# ACL_Shield_V3.net
KiCad netlist of a schematic drawn in EAGLE
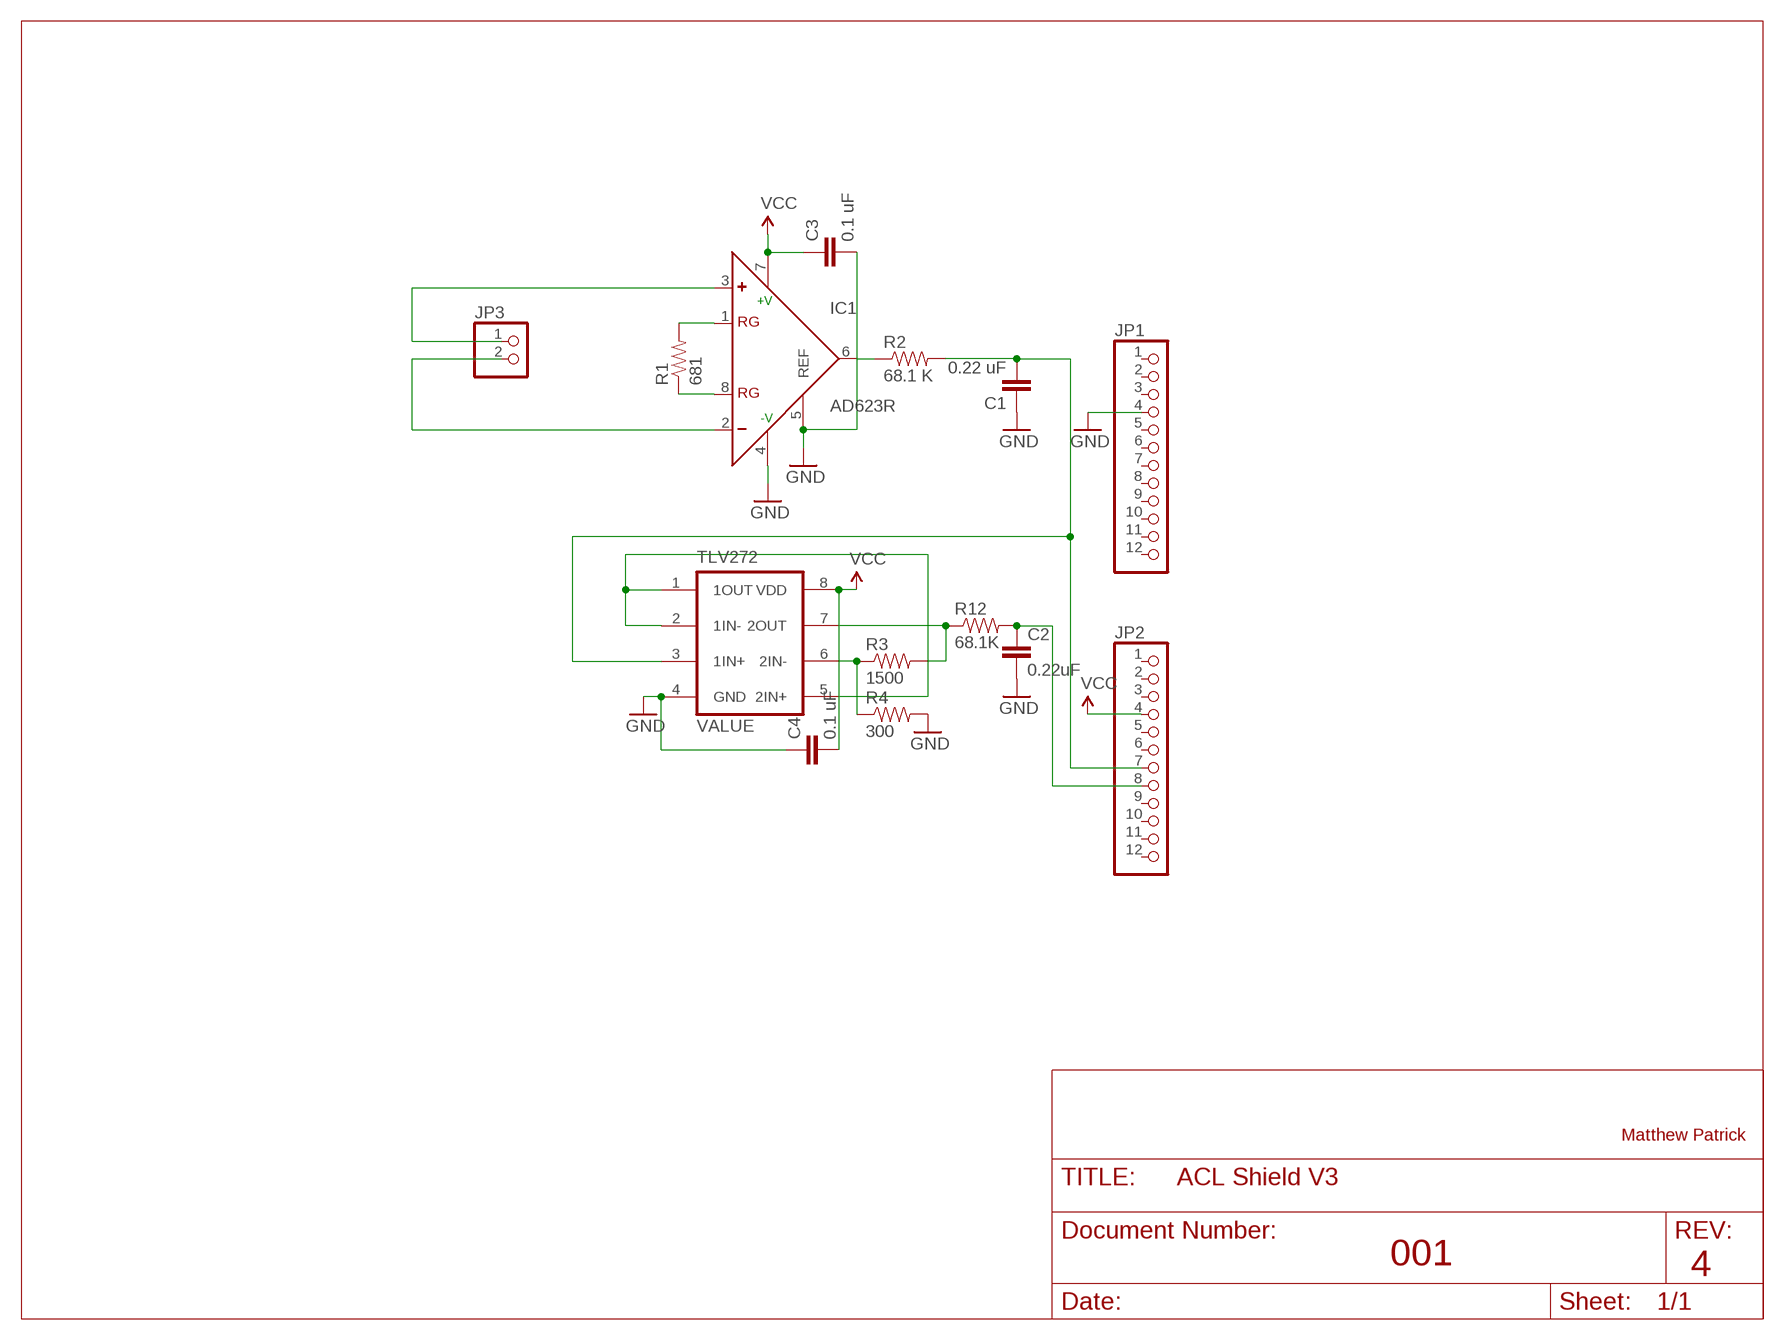
[diagram p0: schematic, sheet 1]

(export (version "E")
  (design (tool "Eeschema 10.0.6"))
  (components
    (comp (ref "C1")
      (value "0.22 uF")
      (footprint "eagle-import:0603-CAP")
      (libsource (lib "eagle-import") (part "CAP0603-CAP"))
    )
    (comp (ref "C2")
      (value "0.22uF")
      (footprint "eagle-import:0603-CAP")
      (libsource (lib "eagle-import") (part "CAP0603-CAP"))
    )
    (comp (ref "C3")
      (value "0.1 uF")
      (footprint "eagle-import:0603-CAP")
      (libsource (lib "eagle-import") (part "CAP0603-CAP"))
    )
    (comp (ref "C4")
      (value "0.1 uF")
      (footprint "eagle-import:0603-CAP")
      (libsource (lib "eagle-import") (part "CAP0603-CAP"))
    )
    (comp (ref "IC1")
      (value "AD623R")
      (footprint "eagle-import:SO8")
      (fields (field (name "MPN") "AD623ARZ."))
      (libsource (lib "eagle-import") (part "AD623R"))
    )
    (comp (ref "JP1")
      (value "PINHD-1X12")
      (footprint "eagle-import:1X12")
      (libsource (lib "eagle-import") (part "PINHD-1X12"))
    )
    (comp (ref "JP2")
      (value "PINHD-1X12")
      (footprint "eagle-import:1X12")
      (libsource (lib "eagle-import") (part "PINHD-1X12"))
    )
    (comp (ref "JP3")
      (value "PINHD-1X2")
      (footprint "eagle-import:1X02")
      (libsource (lib "eagle-import") (part "PINHD-1X2"))
    )
    (comp (ref "R1")
      (value "681")
      (footprint "eagle-import:0603-RES")
      (libsource (lib "eagle-import") (part "RESISTOR0603-RES"))
    )
    (comp (ref "R2")
      (value "68.1 K")
      (footprint "eagle-import:0603-RES")
      (libsource (lib "eagle-import") (part "RESISTOR0603-RES"))
    )
    (comp (ref "R3")
      (value "1500")
      (footprint "eagle-import:0603-RES")
      (libsource (lib "eagle-import") (part "RESISTOR0603-RES"))
    )
    (comp (ref "R4")
      (value "300")
      (footprint "eagle-import:0603-RES")
      (libsource (lib "eagle-import") (part "RESISTOR0603-RES"))
    )
    (comp (ref "R12")
      (value "68.1K")
      (footprint "eagle-import:0603-RES")
      (libsource (lib "eagle-import") (part "RESISTOR0603-RES"))
    )
    (comp (ref "U$2")
      (value "T2721")
      (footprint "eagle-import:SO-08")
      (libsource (lib "eagle-import") (part "T2721"))
    )
  )
  (nets
    (net (code "1") (name "GND") (class "Default")
      (node (ref "C1") (pin "1") (pinfunction "1_1") (pintype "passive"))
      (node (ref "C2") (pin "2") (pinfunction "2_2") (pintype "passive"))
      (node (ref "C3") (pin "2") (pinfunction "2_2") (pintype "passive"))
      (node (ref "C4") (pin "1") (pinfunction "1_1") (pintype "passive"))
      (node (ref "IC1") (pin "4") (pinfunction "-V_4") (pintype "power_in"))
      (node (ref "IC1") (pin "5") (pinfunction "REF_5") (pintype "passive"))
      (node (ref "JP1") (pin "4") (pinfunction "4_4") (pintype "passive"))
      (node (ref "R4") (pin "2") (pinfunction "2_2") (pintype "passive"))
      (node (ref "U$2") (pin "4") (pinfunction "GND_4") (pintype "bidirectional"))
    )
    (net (code "2") (name "Net-(C2-Pad1)") (class "Default")
      (node (ref "C2") (pin "1") (pinfunction "1_1") (pintype "passive"))
      (node (ref "JP2") (pin "8") (pinfunction "8_8") (pintype "passive"))
      (node (ref "R12") (pin "2") (pinfunction "2_2") (pintype "passive"))
    )
    (net (code "3") (name "Net-(IC1-+)") (class "Default")
      (node (ref "IC1") (pin "3") (pinfunction "+_3") (pintype "input"))
      (node (ref "JP3") (pin "1") (pinfunction "1_1") (pintype "passive"))
    )
    (net (code "4") (name "Net-(IC1--)") (class "Default")
      (node (ref "IC1") (pin "2") (pinfunction "-_2") (pintype "input"))
      (node (ref "JP3") (pin "2") (pinfunction "2_2") (pintype "passive"))
    )
    (net (code "5") (name "Net-(IC1-OUT)") (class "Default")
      (node (ref "IC1") (pin "6") (pinfunction "OUT_6") (pintype "output"))
      (node (ref "R2") (pin "1") (pinfunction "1_1") (pintype "passive"))
    )
    (net (code "6") (name "Net-(IC1-RG-Pad1)") (class "Default")
      (node (ref "IC1") (pin "1") (pinfunction "RG_1") (pintype "passive"))
      (node (ref "R1") (pin "2") (pinfunction "2_2") (pintype "passive"))
    )
    (net (code "7") (name "Net-(IC1-RG-Pad8)") (class "Default")
      (node (ref "IC1") (pin "8") (pinfunction "RG_8") (pintype "passive"))
      (node (ref "R1") (pin "1") (pinfunction "1_1") (pintype "passive"))
    )
    (net (code "8") (name "Net-(U$2-1IN+)") (class "Default")
      (node (ref "C1") (pin "2") (pinfunction "2_2") (pintype "passive"))
      (node (ref "JP2") (pin "7") (pinfunction "7_7") (pintype "passive"))
      (node (ref "R2") (pin "2") (pinfunction "2_2") (pintype "passive"))
      (node (ref "U$2") (pin "3") (pinfunction "1IN+_3") (pintype "bidirectional"))
    )
    (net (code "9") (name "Net-(U$2-1IN-)") (class "Default")
      (node (ref "U$2") (pin "1") (pinfunction "1OUT_1") (pintype "bidirectional"))
      (node (ref "U$2") (pin "2") (pinfunction "1IN-_2") (pintype "bidirectional"))
      (node (ref "U$2") (pin "5") (pinfunction "2IN+_5") (pintype "bidirectional"))
    )
    (net (code "10") (name "Net-(U$2-2IN-)") (class "Default")
      (node (ref "R3") (pin "1") (pinfunction "1_1") (pintype "passive"))
      (node (ref "R4") (pin "1") (pinfunction "1_1") (pintype "passive"))
      (node (ref "U$2") (pin "6") (pinfunction "2IN-_6") (pintype "bidirectional"))
    )
    (net (code "11") (name "Net-(U$2-2OUT)") (class "Default")
      (node (ref "R12") (pin "1") (pinfunction "1_1") (pintype "passive"))
      (node (ref "R3") (pin "2") (pinfunction "2_2") (pintype "passive"))
      (node (ref "U$2") (pin "7") (pinfunction "2OUT_7") (pintype "bidirectional"))
    )
    (net (code "12") (name "VCC") (class "Default")
      (node (ref "C3") (pin "1") (pinfunction "1_1") (pintype "passive"))
      (node (ref "C4") (pin "2") (pinfunction "2_2") (pintype "passive"))
      (node (ref "IC1") (pin "7") (pinfunction "+V_7") (pintype "power_in"))
      (node (ref "JP2") (pin "4") (pinfunction "4_4") (pintype "passive"))
      (node (ref "U$2") (pin "8") (pinfunction "VDD_8") (pintype "bidirectional"))
    )
    (net (code "13") (name "unconnected-(JP1-Pad1)") (class "Default")
      (node (ref "JP1") (pin "1") (pinfunction "1_1") (pintype "passive"))
    )
    (net (code "14") (name "unconnected-(JP1-Pad2)") (class "Default")
      (node (ref "JP1") (pin "2") (pinfunction "2_2") (pintype "passive"))
    )
    (net (code "15") (name "unconnected-(JP1-Pad3)") (class "Default")
      (node (ref "JP1") (pin "3") (pinfunction "3_3") (pintype "passive"))
    )
    (net (code "16") (name "unconnected-(JP1-Pad5)") (class "Default")
      (node (ref "JP1") (pin "5") (pinfunction "5_5") (pintype "passive"))
    )
    (net (code "17") (name "unconnected-(JP1-Pad6)") (class "Default")
      (node (ref "JP1") (pin "6") (pinfunction "6_6") (pintype "passive"))
    )
    (net (code "18") (name "unconnected-(JP1-Pad7)") (class "Default")
      (node (ref "JP1") (pin "7") (pinfunction "7_7") (pintype "passive"))
    )
    (net (code "19") (name "unconnected-(JP1-Pad8)") (class "Default")
      (node (ref "JP1") (pin "8") (pinfunction "8_8") (pintype "passive"))
    )
    (net (code "20") (name "unconnected-(JP1-Pad9)") (class "Default")
      (node (ref "JP1") (pin "9") (pinfunction "9_9") (pintype "passive"))
    )
    (net (code "21") (name "unconnected-(JP1-Pad10)") (class "Default")
      (node (ref "JP1") (pin "10") (pinfunction "10_10") (pintype "passive"))
    )
    (net (code "22") (name "unconnected-(JP1-Pad11)") (class "Default")
      (node (ref "JP1") (pin "11") (pinfunction "11_11") (pintype "passive"))
    )
    (net (code "23") (name "unconnected-(JP1-Pad12)") (class "Default")
      (node (ref "JP1") (pin "12") (pinfunction "12_12") (pintype "passive"))
    )
    (net (code "24") (name "unconnected-(JP2-Pad1)") (class "Default")
      (node (ref "JP2") (pin "1") (pinfunction "1_1") (pintype "passive"))
    )
    (net (code "25") (name "unconnected-(JP2-Pad2)") (class "Default")
      (node (ref "JP2") (pin "2") (pinfunction "2_2") (pintype "passive"))
    )
    (net (code "26") (name "unconnected-(JP2-Pad3)") (class "Default")
      (node (ref "JP2") (pin "3") (pinfunction "3_3") (pintype "passive"))
    )
    (net (code "27") (name "unconnected-(JP2-Pad5)") (class "Default")
      (node (ref "JP2") (pin "5") (pinfunction "5_5") (pintype "passive"))
    )
    (net (code "28") (name "unconnected-(JP2-Pad6)") (class "Default")
      (node (ref "JP2") (pin "6") (pinfunction "6_6") (pintype "passive"))
    )
    (net (code "29") (name "unconnected-(JP2-Pad9)") (class "Default")
      (node (ref "JP2") (pin "9") (pinfunction "9_9") (pintype "passive"))
    )
    (net (code "30") (name "unconnected-(JP2-Pad10)") (class "Default")
      (node (ref "JP2") (pin "10") (pinfunction "10_10") (pintype "passive"))
    )
    (net (code "31") (name "unconnected-(JP2-Pad11)") (class "Default")
      (node (ref "JP2") (pin "11") (pinfunction "11_11") (pintype "passive"))
    )
    (net (code "32") (name "unconnected-(JP2-Pad12)") (class "Default")
      (node (ref "JP2") (pin "12") (pinfunction "12_12") (pintype "passive"))
    )
  )
)
